# Buck_Converter.net
KiCad netlist of a schematic drawn in Altium Designer
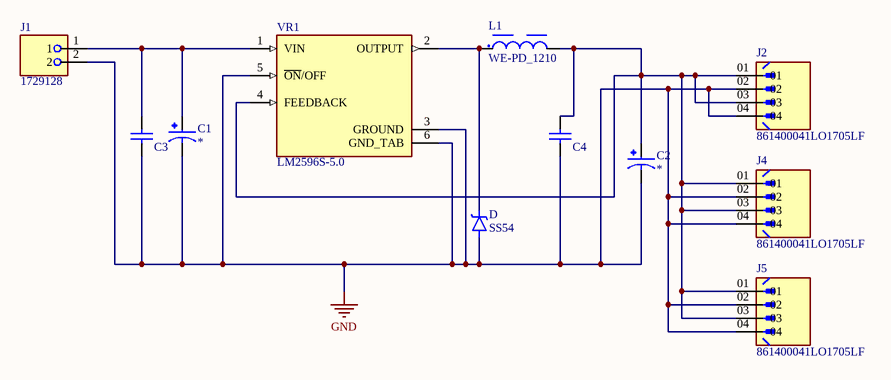
[diagram p0: Buck Converter.SchDoc]

(export (version "E")
  (design (tool "Eeschema 10.0.6"))
  (components
    (comp (ref "C1")
      (value "EEEFK1V221P")
      (footprint "CAP_EEEFK1V221P")
      (description "220ÂµF 35V Aluminum Electrolytic Capacitors Radial, Can - SMD 2000 Hrs @ 105Â°C")
      (fields (field (name "ALTIUM_VALUE") "*") (field (name "MF") "Panasonic"))
      (libsource (lib "Kaitlynnly") (part "EEEFK1V221P"))
    )
    (comp (ref "C2")
      (value "EEEFK1V221P")
      (footprint "CAP_EEEFK1V221P")
      (description "220ÂµF 35V Aluminum Electrolytic Capacitors Radial, Can - SMD 2000 Hrs @ 105Â°C")
      (fields (field (name "ALTIUM_VALUE") "*") (field (name "MF") "Panasonic"))
      (libsource (lib "Kaitlynnly") (part "EEEFK1V221P"))
    )
    (comp (ref "C3")
      (value "GRM188R71H104KA93D")
      (footprint "CAPC1608X90X35ML10T15")
      (description "Multilayer Ceramic Capacitors MLCC Surface Mount 0603 0.1uF 50 Volts X7R 10%")
      (libsource (lib "Kaitlynnly") (part "CAP-NP-2"))
    )
    (comp (ref "C4")
      (value "GRM188R71H104KA93D")
      (footprint "CAPC1608X90X35ML10T15")
      (description "Multilayer Ceramic Capacitors MLCC Surface Mount 0603 0.1uF 50 Volts X7R 10%")
      (libsource (lib "Kaitlynnly") (part "CAP-NP-2"))
    )
    (comp (ref "D")
      (value "SS54")
      (footprint "DO-214AC")
      (description "Digital Switch Unipolar Switch Open Collector Hall Effect SOT-89B")
      (fields (field (name "MF") "Honeywell Sensing"))
      (libsource (lib "Kaitlynnly") (part "SS54"))
    )
    (comp (ref "J1")
      (value "1729128")
      (footprint "PHOENIX_1729128")
      (description "PCB Terminal Screw 5.08mm 16AWG 400V 13.5A 2 Position COMBICON MKDSN Series")
      (fields (field (name "MF") "Phoenix Contact"))
      (libsource (lib "Kaitlynnly") (part "1729128"))
    )
    (comp (ref "J2")
      (value "861400041LO1705LF")
      (footprint "AMPHENOL_861400041LO1705LF")
      (description "Board to Board connector, Unshrouded Header, Through Hole, Single Row, 4 Position, Right Angle.")
      (fields (field (name "MF") "Amphenol ICC (FCI)"))
      (libsource (lib "Kaitlynnly") (part "861400041LO1705LF"))
    )
    (comp (ref "J4")
      (value "861400041LO1705LF")
      (footprint "AMPHENOL_861400041LO1705LF")
      (description "Board to Board connector, Unshrouded Header, Through Hole, Single Row, 4 Position, Right Angle.")
      (fields (field (name "MF") "Amphenol ICC (FCI)"))
      (libsource (lib "Kaitlynnly") (part "861400041LO1705LF"))
    )
    (comp (ref "J5")
      (value "861400041LO1705LF")
      (footprint "AMPHENOL_861400041LO1705LF")
      (description "Board to Board connector, Unshrouded Header, Through Hole, Single Row, 4 Position, Right Angle.")
      (fields (field (name "MF") "Amphenol ICC (FCI)"))
      (libsource (lib "Kaitlynnly") (part "861400041LO1705LF"))
    )
    (comp (ref "L1")
      (value "WE-PD_1210")
      (footprint "WE-PD_1210")
      (fields
        (field (name "MF") "{'manufacturer': u'~{W}xfcrth Elektronik'}")
        (field (name "MP") "7447709330")
      )
      (libsource (lib "WE-PD_1210") (part "WE-PD_1210"))
    )
    (comp (ref "VR1")
      (value "LM2596S-5.0")
      (footprint "TO170P1524X483-6N")
      (description "SIMPLE SWITCHERÂ® 4.5V to 40V, 3A Low Component Count Step-Down Regulator")
      (fields (field (name "MF") "Texas Instruments") (field (name "MP") "LM2596S-5.0/NOPB"))
      (libsource (lib "Kaitlynnly") (part "LM2596S-5.0"))
    )
  )
  (nets
    (net (code "1") (name "GND") (class "Default")
      (node (ref "C1") (pin "2") (pinfunction "2_2") (pintype "passive"))
      (node (ref "C2") (pin "2") (pinfunction "2_2") (pintype "passive"))
      (node (ref "C3") (pin "1") (pinfunction "1_1") (pintype "passive"))
      (node (ref "C4") (pin "1") (pinfunction "1_1") (pintype "passive"))
      (node (ref "D") (pin "A") (pinfunction "A_A") (pintype "passive"))
      (node (ref "J1") (pin "2") (pinfunction "2_2") (pintype "passive"))
      (node (ref "J2") (pin "02") (pinfunction "02_02") (pintype "passive"))
      (node (ref "J2") (pin "04") (pinfunction "04_04") (pintype "passive"))
      (node (ref "J4") (pin "02") (pinfunction "02_02") (pintype "passive"))
      (node (ref "J4") (pin "04") (pinfunction "04_04") (pintype "passive"))
      (node (ref "J5") (pin "02") (pinfunction "02_02") (pintype "passive"))
      (node (ref "J5") (pin "04") (pinfunction "04_04") (pintype "passive"))
      (node (ref "VR1") (pin "3") (pinfunction "GROUND_3") (pintype "power_in"))
      (node (ref "VR1") (pin "5") (pinfunction "~{ON}/OFF_5") (pintype "input"))
      (node (ref "VR1") (pin "6") (pinfunction "GND_TAB_6") (pintype "power_in"))
    )
    (net (code "2") (name "Net-(VR1-FEEDBACK)") (class "Default")
      (node (ref "C2") (pin "1") (pinfunction "1_1") (pintype "passive"))
      (node (ref "C4") (pin "2") (pinfunction "2_2") (pintype "passive"))
      (node (ref "J2") (pin "01") (pinfunction "01_01") (pintype "passive"))
      (node (ref "J2") (pin "03") (pinfunction "03_03") (pintype "passive"))
      (node (ref "J4") (pin "01") (pinfunction "01_01") (pintype "passive"))
      (node (ref "J4") (pin "03") (pinfunction "03_03") (pintype "passive"))
      (node (ref "J5") (pin "01") (pinfunction "01_01") (pintype "passive"))
      (node (ref "J5") (pin "03") (pinfunction "03_03") (pintype "passive"))
      (node (ref "L1") (pin "2") (pinfunction "2_2") (pintype "passive"))
      (node (ref "VR1") (pin "4") (pinfunction "FEEDBACK_4") (pintype "input"))
    )
    (net (code "3") (name "Net-(VR1-OUTPUT)") (class "Default")
      (node (ref "D") (pin "C") (pinfunction "C_C") (pintype "passive"))
      (node (ref "L1") (pin "1") (pinfunction "1_1") (pintype "passive"))
      (node (ref "VR1") (pin "2") (pinfunction "OUTPUT_2") (pintype "output"))
    )
    (net (code "4") (name "Net-(VR1-VIN)") (class "Default")
      (node (ref "C1") (pin "1") (pinfunction "1_1") (pintype "passive"))
      (node (ref "C3") (pin "2") (pinfunction "2_2") (pintype "passive"))
      (node (ref "J1") (pin "1") (pinfunction "1_1") (pintype "passive"))
      (node (ref "VR1") (pin "1") (pinfunction "VIN_1") (pintype "input"))
    )
  )
)
